# Desk_lamp.net
KiCad netlist of a schematic drawn in Altium Designer
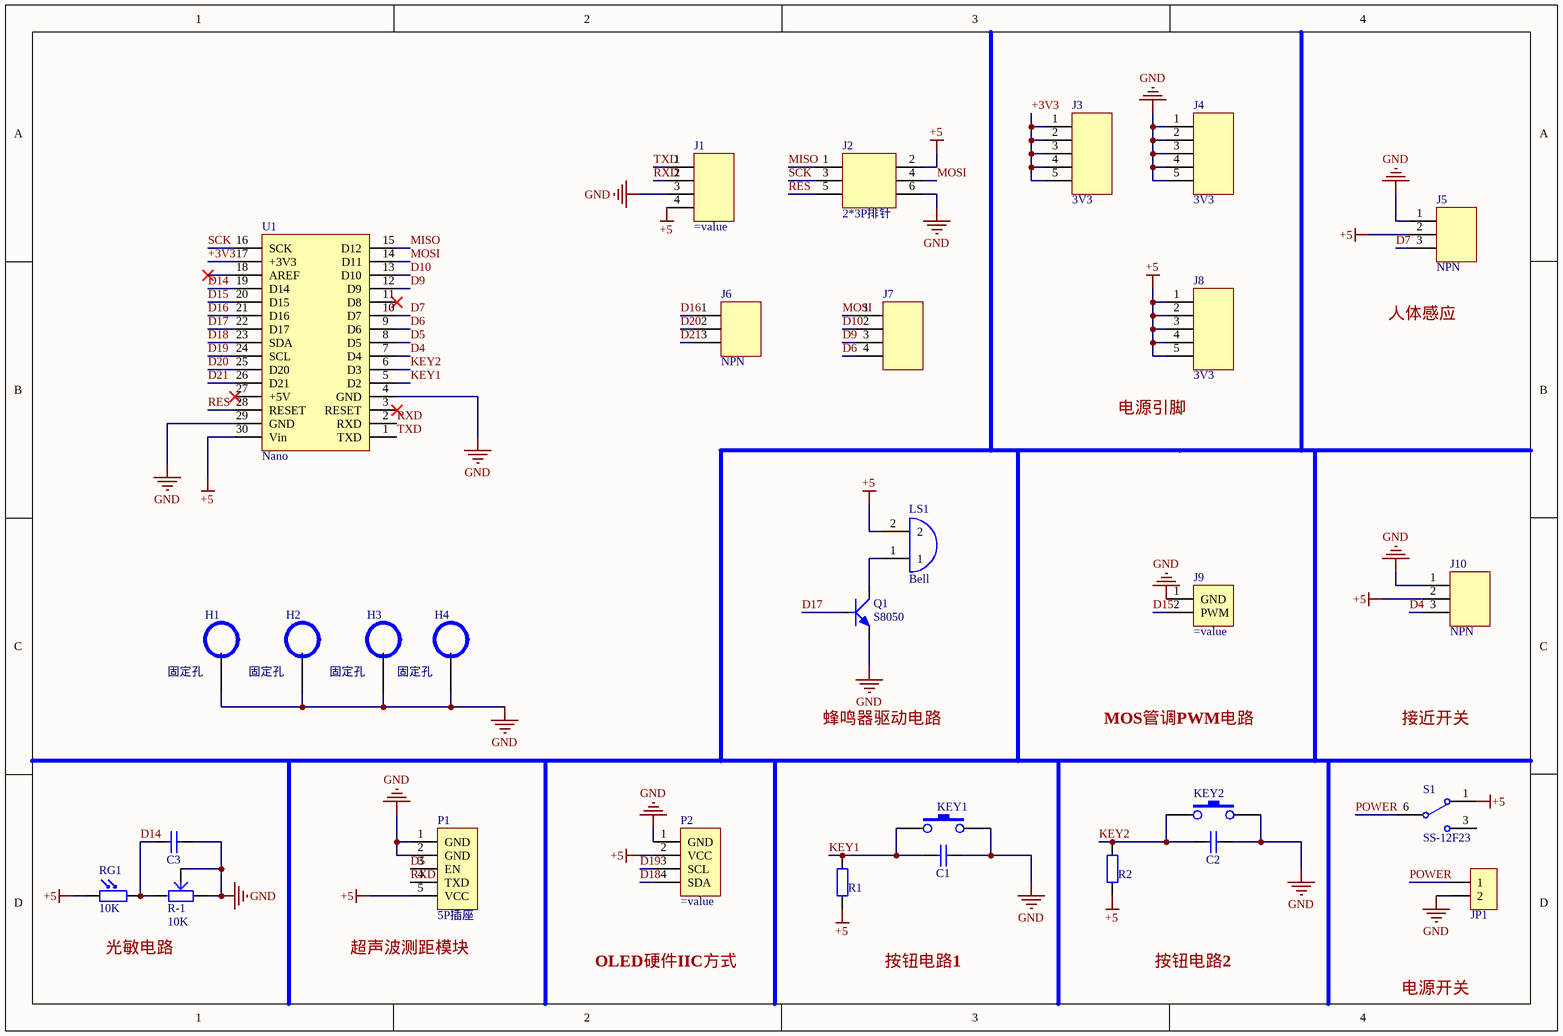
[diagram p0: Desk lamp原理图.SchDoc]

(export (version "E")
  (design (tool "Eeschema 10.0.6"))
  (components
    (comp (ref "C1")
      (value "~")
      (footprint "C 0805_L")
      (description "无极性电容")
      (libsource (lib "Desk lamp原理图库") (part "Cap"))
    )
    (comp (ref "C2")
      (value "~")
      (footprint "C 0805_L")
      (description "无极性电容")
      (libsource (lib "Desk lamp原理图库") (part "Cap"))
    )
    (comp (ref "C3")
      (value "~")
      (footprint "C 0805_L")
      (description "无极性电容")
      (libsource (lib "Desk lamp原理图库") (part "Cap"))
    )
    (comp (ref "H1") (value "固定孔") (footprint "M3x6+6_L") (libsource (lib "Desk lamp原理图库") (part "固定孔")))
    (comp (ref "H2") (value "固定孔") (footprint "M3x6+6_L") (libsource (lib "Desk lamp原理图库") (part "固定孔")))
    (comp (ref "H3") (value "固定孔") (footprint "M3x6+6_L") (libsource (lib "Desk lamp原理图库") (part "固定孔")))
    (comp (ref "H4") (value "固定孔") (footprint "M3x6+6_L") (libsource (lib "Desk lamp原理图库") (part "固定孔")))
    (comp (ref "J1")
      (value "~")
      (footprint "XH2.54-LI-4P")
      (description "2.54插座")
      (libsource (lib "Desk lamp原理图库") (part "4P插座"))
    )
    (comp (ref "J2")
      (value "2*3P排针")
      (footprint "HDR2.54-LI-2x3P")
      (description "双排针")
      (libsource (lib "Desk lamp原理图库") (part "2*3P排针"))
    )
    (comp (ref "J3")
      (value "3V3")
      (footprint "HDR2.54-LI-5P")
      (description "2.54排针")
      (libsource (lib "Desk lamp原理图库") (part "5P排针"))
    )
    (comp (ref "J4")
      (value "3V3")
      (footprint "HDR2.54-LI-5P")
      (description "2.54排针")
      (libsource (lib "Desk lamp原理图库") (part "5P排针"))
    )
    (comp (ref "J5")
      (value "NPN")
      (footprint "HDR2.54-LI-3P")
      (description "2.54插座")
      (libsource (lib "Desk lamp原理图库") (part "3P插座"))
    )
    (comp (ref "J6")
      (value "NPN")
      (footprint "HDR2.54-LI-3P")
      (description "2.54插座")
      (libsource (lib "Desk lamp原理图库") (part "3P插座"))
    )
    (comp (ref "J7")
      (value "~")
      (footprint "XH2.54-LI-4P")
      (description "2.54插座")
      (libsource (lib "Desk lamp原理图库") (part "4P插座"))
    )
    (comp (ref "J8")
      (value "3V3")
      (footprint "HDR2.54-LI-5P")
      (description "2.54排针")
      (libsource (lib "Desk lamp原理图库") (part "5P排针"))
    )
    (comp (ref "J9")
      (value "~")
      (footprint "XH2.54-LI-2P")
      (description "2.54插座")
      (libsource (lib "Desk lamp原理图库") (part "MOS管"))
    )
    (comp (ref "J10")
      (value "NPN")
      (footprint "HDR2.54-LI-3P")
      (description "2.54插座")
      (libsource (lib "Desk lamp原理图库") (part "3P插座"))
    )
    (comp (ref "JP1")
      (value "HDR-1X2")
      (footprint "HT3.96-WI-2P-ORG")
      (description "2P接插件")
      (libsource (lib "4.9   - 接插件-脚距3.96") (part "Header 2"))
    )
    (comp (ref "KEY1")
      (value "KEY")
      (footprint "_key_")
      (description "按钮")
      (libsource (lib "Desk lamp原理图库") (part "KEY"))
    )
    (comp (ref "KEY2")
      (value "KEY")
      (footprint "_key_")
      (description "按钮")
      (libsource (lib "Desk lamp原理图库") (part "KEY"))
    )
    (comp (ref "LS1")
      (value "Bell")
      (footprint "BEEP 7.6x12x9.5")
      (description "Electrical Bell")
      (fields (field (name "PUBLISHER") "Altium Limited"))
      (libsource (lib "Desk lamp原理图库") (part "Bell"))
    )
    (comp (ref "P1")
      (value "5P插座")
      (footprint "XH2.54-LI-5P")
      (description "2.54插座")
      (libsource (lib "Desk lamp原理图库") (part "5P插座"))
    )
    (comp (ref "P2")
      (value "~")
      (footprint "XH2.54-LI-4P")
      (description "显示屏")
      (libsource (lib "Desk lamp原理图库") (part "OLED"))
    )
    (comp (ref "Q1") (value "S8050") (footprint "SOT23-3L") (libsource (lib "Desk lamp原理图库") (part "S8050")))
    (comp (ref "R-1") (value "10K") (footprint "3319P") (libsource (lib "Desk lamp原理图库") (part "电位器")))
    (comp (ref "R1")
      (value "10K")
      (footprint "R 0603")
      (description "电阻")
      (libsource (lib "Desk lamp原理图库") (part "Res"))
    )
    (comp (ref "R2")
      (value "10K")
      (footprint "R 0603")
      (description "电阻")
      (libsource (lib "Desk lamp原理图库") (part "Res"))
    )
    (comp (ref "RG1")
      (value "10K")
      (footprint "RG5528")
      (description "光敏电阻")
      (libsource (lib "Desk lamp原理图库") (part "RG5528"))
    )
    (comp (ref "S1")
      (value "SS-12F23")
      (footprint "KFC DIP-8X8")
      (description "1路波动开关")
      (libsource (lib "Desk lamp原理图库") (part "SSW-1P"))
    )
    (comp (ref "U1")
      (value "Nano")
      (footprint "Nano")
      (description "Arduino")
      (libsource (lib "Desk lamp原理图库") (part "Nano"))
    )
  )
  (nets
    (net (code "1") (name "+5") (class "Default")
      (node (ref "J1") (pin "4") (pinfunction "SDA_4") (pintype "passive"))
      (node (ref "J10") (pin "2") (pinfunction "VCC_2") (pintype "passive"))
      (node (ref "J2") (pin "2") (pinfunction "GND_2") (pintype "passive"))
      (node (ref "J5") (pin "2") (pinfunction "VCC_2") (pintype "passive"))
      (node (ref "J8") (pin "1") (pinfunction "GND_1") (pintype "passive"))
      (node (ref "J8") (pin "2") (pinfunction "GND_2") (pintype "passive"))
      (node (ref "J8") (pin "3") (pinfunction "GND_3") (pintype "passive"))
      (node (ref "J8") (pin "4") (pinfunction "GND_4") (pintype "passive"))
      (node (ref "J8") (pin "5") (pinfunction "GND_5") (pintype "passive"))
      (node (ref "LS1") (pin "2") (pinfunction "2_2") (pintype "passive"))
      (node (ref "P1") (pin "5") (pinfunction "VCC_5") (pintype "passive"))
      (node (ref "P2") (pin "2") (pinfunction "VCC_2") (pintype "passive"))
      (node (ref "R1") (pin "1") (pinfunction "1_1") (pintype "passive"))
      (node (ref "R2") (pin "1") (pinfunction "1_1") (pintype "passive"))
      (node (ref "RG1") (pin "1") (pinfunction "1_1") (pintype "passive"))
      (node (ref "S1") (pin "1") (pinfunction "1_1") (pintype "passive"))
      (node (ref "U1") (pin "30") (pinfunction "Vin_30") (pintype "passive"))
    )
    (net (code "2") (name "/+3V3") (class "Default")
      (node (ref "J3") (pin "1") (pinfunction "GND_1") (pintype "passive"))
      (node (ref "J3") (pin "2") (pinfunction "GND_2") (pintype "passive"))
      (node (ref "J3") (pin "3") (pinfunction "GND_3") (pintype "passive"))
      (node (ref "J3") (pin "4") (pinfunction "GND_4") (pintype "passive"))
      (node (ref "J3") (pin "5") (pinfunction "GND_5") (pintype "passive"))
      (node (ref "U1") (pin "17") (pinfunction "+3V3_17") (pintype "passive"))
    )
    (net (code "3") (name "/D4") (class "Default")
      (node (ref "J10") (pin "3") (pinfunction "DC_3") (pintype "passive"))
      (node (ref "U1") (pin "7") (pinfunction "D4_7") (pintype "passive"))
    )
    (net (code "4") (name "/D5") (class "Default")
      (node (ref "P1") (pin "3") (pinfunction "EN_3") (pintype "passive"))
      (node (ref "U1") (pin "8") (pinfunction "D5_8") (pintype "passive"))
    )
    (net (code "5") (name "/D6") (class "Default")
      (node (ref "J7") (pin "4") (pinfunction "SDA_4") (pintype "passive"))
      (node (ref "U1") (pin "9") (pinfunction "D6_9") (pintype "passive"))
    )
    (net (code "6") (name "/D7") (class "Default")
      (node (ref "J5") (pin "3") (pinfunction "DC_3") (pintype "passive"))
      (node (ref "U1") (pin "10") (pinfunction "D7_10") (pintype "passive"))
    )
    (net (code "7") (name "/D9") (class "Default")
      (node (ref "J7") (pin "3") (pinfunction "SCL_3") (pintype "passive"))
      (node (ref "U1") (pin "12") (pinfunction "D9_12") (pintype "passive"))
    )
    (net (code "8") (name "/D10") (class "Default")
      (node (ref "J7") (pin "2") (pinfunction "VCC_2") (pintype "passive"))
      (node (ref "U1") (pin "13") (pinfunction "D10_13") (pintype "passive"))
    )
    (net (code "9") (name "/D14") (class "Default")
      (node (ref "C3") (pin "1") (pinfunction "1_1") (pintype "passive"))
      (node (ref "R-1") (pin "1") (pinfunction "1_1") (pintype "passive"))
      (node (ref "RG1") (pin "2") (pinfunction "2_2") (pintype "passive"))
      (node (ref "U1") (pin "19") (pinfunction "D14_19") (pintype "passive"))
    )
    (net (code "10") (name "/D15") (class "Default")
      (node (ref "J9") (pin "2") (pinfunction "PWM_2") (pintype "passive"))
      (node (ref "U1") (pin "20") (pinfunction "D15_20") (pintype "passive"))
    )
    (net (code "11") (name "/D16") (class "Default")
      (node (ref "J6") (pin "1") (pinfunction "GND_1") (pintype "passive"))
      (node (ref "U1") (pin "21") (pinfunction "D16_21") (pintype "passive"))
    )
    (net (code "12") (name "/D17") (class "Default")
      (node (ref "Q1") (pin "3") (pinfunction "3_3") (pintype "passive"))
      (node (ref "U1") (pin "22") (pinfunction "D17_22") (pintype "passive"))
    )
    (net (code "13") (name "/D18") (class "Default")
      (node (ref "P2") (pin "4") (pinfunction "SDA_4") (pintype "passive"))
      (node (ref "U1") (pin "23") (pinfunction "SDA_23") (pintype "passive"))
    )
    (net (code "14") (name "/D19") (class "Default")
      (node (ref "P2") (pin "3") (pinfunction "SCL_3") (pintype "passive"))
      (node (ref "U1") (pin "24") (pinfunction "SCL_24") (pintype "passive"))
    )
    (net (code "15") (name "/D20") (class "Default")
      (node (ref "J6") (pin "2") (pinfunction "VCC_2") (pintype "passive"))
      (node (ref "U1") (pin "25") (pinfunction "D20_25") (pintype "passive"))
    )
    (net (code "16") (name "/D21") (class "Default")
      (node (ref "J6") (pin "3") (pinfunction "DC_3") (pintype "passive"))
      (node (ref "U1") (pin "26") (pinfunction "D21_26") (pintype "passive"))
    )
    (net (code "17") (name "/KEY1") (class "Default")
      (node (ref "C1") (pin "1") (pinfunction "1_1") (pintype "passive"))
      (node (ref "KEY1") (pin "1") (pinfunction "1_1") (pintype "passive"))
      (node (ref "R1") (pin "2") (pinfunction "2_2") (pintype "passive"))
      (node (ref "U1") (pin "5") (pinfunction "D2_5") (pintype "passive"))
    )
    (net (code "18") (name "/KEY2") (class "Default")
      (node (ref "C2") (pin "1") (pinfunction "1_1") (pintype "passive"))
      (node (ref "KEY2") (pin "1") (pinfunction "1_1") (pintype "passive"))
      (node (ref "R2") (pin "2") (pinfunction "2_2") (pintype "passive"))
      (node (ref "U1") (pin "6") (pinfunction "D3_6") (pintype "passive"))
    )
    (net (code "19") (name "/MISO") (class "Default")
      (node (ref "J2") (pin "1") (pinfunction "GND_1") (pintype "passive"))
      (node (ref "U1") (pin "15") (pinfunction "D12_15") (pintype "passive"))
    )
    (net (code "20") (name "/MOSI") (class "Default")
      (node (ref "J2") (pin "4") (pinfunction "GND_4") (pintype "passive"))
      (node (ref "J7") (pin "1") (pinfunction "GND_1") (pintype "passive"))
      (node (ref "U1") (pin "14") (pinfunction "D11_14") (pintype "passive"))
    )
    (net (code "21") (name "/POWER") (class "Default")
      (node (ref "JP1") (pin "1") (pinfunction "1_1") (pintype "passive"))
      (node (ref "S1") (pin "6") (pinfunction "6_6") (pintype "passive"))
    )
    (net (code "22") (name "/RES") (class "Default")
      (node (ref "J2") (pin "5") (pinfunction "DC_5") (pintype "passive"))
      (node (ref "U1") (pin "28") (pinfunction "RESET_28") (pintype "passive"))
    )
    (net (code "23") (name "/RXD") (class "Default")
      (node (ref "J1") (pin "2") (pinfunction "VCC_2") (pintype "passive"))
      (node (ref "P1") (pin "4") (pinfunction "TXD_4") (pintype "passive"))
      (node (ref "U1") (pin "2") (pinfunction "RXD_2") (pintype "passive"))
    )
    (net (code "24") (name "/SCK") (class "Default")
      (node (ref "J2") (pin "3") (pinfunction "VCC_3") (pintype "passive"))
      (node (ref "U1") (pin "16") (pinfunction "SCK_16") (pintype "passive"))
    )
    (net (code "25") (name "/TXD") (class "Default")
      (node (ref "J1") (pin "1") (pinfunction "GND_1") (pintype "passive"))
      (node (ref "U1") (pin "1") (pinfunction "TXD_1") (pintype "passive"))
    )
    (net (code "26") (name "GND") (class "Default")
      (node (ref "C1") (pin "2") (pinfunction "2_2") (pintype "passive"))
      (node (ref "C2") (pin "2") (pinfunction "2_2") (pintype "passive"))
      (node (ref "C3") (pin "2") (pinfunction "2_2") (pintype "passive"))
      (node (ref "H1") (pin "1") (pinfunction "1_1") (pintype "passive"))
      (node (ref "H2") (pin "1") (pinfunction "1_1") (pintype "passive"))
      (node (ref "H3") (pin "1") (pinfunction "1_1") (pintype "passive"))
      (node (ref "H4") (pin "1") (pinfunction "1_1") (pintype "passive"))
      (node (ref "J1") (pin "3") (pinfunction "SCL_3") (pintype "passive"))
      (node (ref "J10") (pin "1") (pinfunction "GND_1") (pintype "passive"))
      (node (ref "J2") (pin "6") (pinfunction "GND_6") (pintype "passive"))
      (node (ref "J4") (pin "1") (pinfunction "GND_1") (pintype "passive"))
      (node (ref "J4") (pin "2") (pinfunction "GND_2") (pintype "passive"))
      (node (ref "J4") (pin "3") (pinfunction "GND_3") (pintype "passive"))
      (node (ref "J4") (pin "4") (pinfunction "GND_4") (pintype "passive"))
      (node (ref "J4") (pin "5") (pinfunction "GND_5") (pintype "passive"))
      (node (ref "J5") (pin "1") (pinfunction "GND_1") (pintype "passive"))
      (node (ref "J9") (pin "1") (pinfunction "GND_1") (pintype "passive"))
      (node (ref "JP1") (pin "2") (pinfunction "2_2") (pintype "passive"))
      (node (ref "KEY1") (pin "2") (pinfunction "3_2") (pintype "passive"))
      (node (ref "KEY2") (pin "2") (pinfunction "3_2") (pintype "passive"))
      (node (ref "P1") (pin "1") (pinfunction "GND_1") (pintype "passive"))
      (node (ref "P1") (pin "2") (pinfunction "GND_2") (pintype "passive"))
      (node (ref "P2") (pin "1") (pinfunction "GND_1") (pintype "passive"))
      (node (ref "Q1") (pin "1") (pinfunction "1_1") (pintype "passive"))
      (node (ref "R-1") (pin "2") (pinfunction "2_2") (pintype "passive"))
      (node (ref "R-1") (pin "3") (pinfunction "3_3") (pintype "passive"))
      (node (ref "U1") (pin "29") (pinfunction "GND_29") (pintype "passive"))
      (node (ref "U1") (pin "4") (pinfunction "GND_4") (pintype "passive"))
    )
    (net (code "27") (name "Net-(LS1-Pad1)") (class "Default")
      (node (ref "LS1") (pin "1") (pinfunction "1_1") (pintype "passive"))
      (node (ref "Q1") (pin "2") (pinfunction "2_2") (pintype "passive"))
    )
    (net (code "28") (name "unconnected-(S1-Pad3)") (class "Default")
      (node (ref "S1") (pin "3") (pinfunction "3_3") (pintype "passive"))
    )
    (net (code "29") (name "unconnected-(U1-+5V-Pad27)") (class "Default")
      (node (ref "U1") (pin "27") (pinfunction "+5V_27") (pintype "passive+no_connect"))
    )
    (net (code "30") (name "unconnected-(U1-AREF-Pad18)") (class "Default")
      (node (ref "U1") (pin "18") (pinfunction "AREF_18") (pintype "passive+no_connect"))
    )
    (net (code "31") (name "unconnected-(U1-D8-Pad11)") (class "Default")
      (node (ref "U1") (pin "11") (pinfunction "D8_11") (pintype "passive+no_connect"))
    )
    (net (code "32") (name "unconnected-(U1-RESET-Pad3)") (class "Default")
      (node (ref "U1") (pin "3") (pinfunction "RESET_3") (pintype "passive+no_connect"))
    )
  )
)
